# main.net
KiCad netlist of a schematic drawn in EAGLE
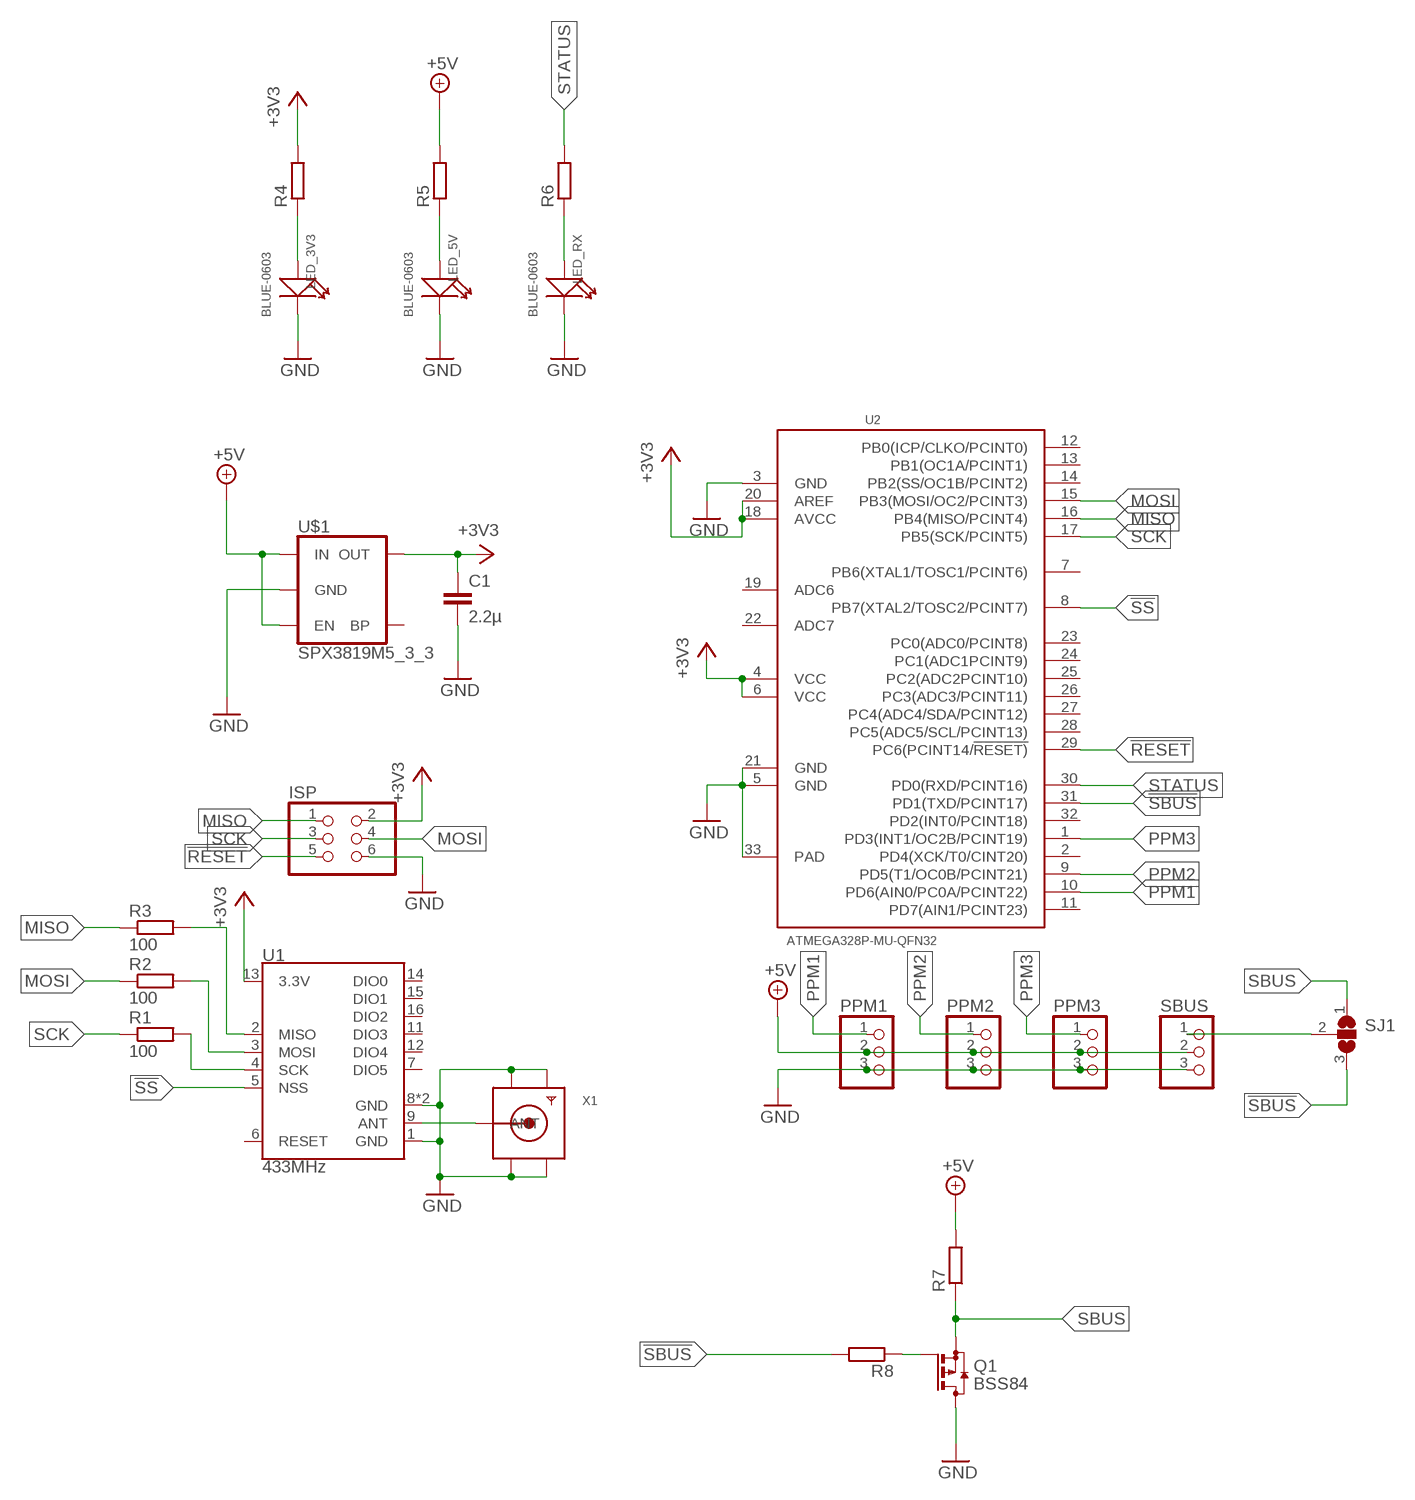
[diagram p0: schematic, sheet 1]

(export (version "E")
  (design (tool "Eeschema 10.0.6"))
  (components
    (comp (ref "C1")
      (value "2.2µ")
      (footprint "eagle-import:C0603")
      (libsource (lib "eagle-import") (part "C-EUC0603"))
    )
    (comp (ref "ISP")
      (value "PINHD-2X3_2.54-SMD")
      (footprint "eagle-import:2X03SMD")
      (libsource (lib "eagle-import") (part "PINHD-2X3_2.54-SMD"))
    )
    (comp (ref "LED_3V3")
      (value "BLUE-0603")
      (footprint "eagle-import:LED-0603")
      (fields (field (name "MPN") "19-217-BHC-ZL1M2RY-3T"))
      (libsource (lib "eagle-import") (part "SMD-LED-CLEAR-BLUE(0603)"))
    )
    (comp (ref "LED_5V")
      (value "BLUE-0603")
      (footprint "eagle-import:LED-0603")
      (fields (field (name "MPN") "19-217-BHC-ZL1M2RY-3T"))
      (libsource (lib "eagle-import") (part "SMD-LED-CLEAR-BLUE(0603)"))
    )
    (comp (ref "LED_RX")
      (value "BLUE-0603")
      (footprint "eagle-import:LED-0603")
      (fields (field (name "MPN") "19-217-BHC-ZL1M2RY-3T"))
      (libsource (lib "eagle-import") (part "SMD-LED-CLEAR-BLUE(0603)"))
    )
    (comp (ref "PPM1")
      (value "PINHD-1X3_2.54-SMD")
      (footprint "eagle-import:1X03SMD")
      (libsource (lib "eagle-import") (part "PINHD-1X3_2.54-SMD"))
    )
    (comp (ref "PPM2")
      (value "PINHD-1X3_2.54-SMD")
      (footprint "eagle-import:1X03SMD")
      (libsource (lib "eagle-import") (part "PINHD-1X3_2.54-SMD"))
    )
    (comp (ref "PPM3")
      (value "PINHD-1X3_2.54-SMD")
      (footprint "eagle-import:1X03SMD")
      (libsource (lib "eagle-import") (part "PINHD-1X3_2.54-SMD"))
    )
    (comp (ref "Q1")
      (value "BSS84")
      (footprint "eagle-import:SOT23")
      (libsource (lib "eagle-import") (part "BSS84"))
    )
    (comp (ref "R1")
      (value "100")
      (footprint "eagle-import:R0603")
      (libsource (lib "eagle-import") (part "R-EU_R0603"))
    )
    (comp (ref "R2")
      (value "100")
      (footprint "eagle-import:R0603")
      (libsource (lib "eagle-import") (part "R-EU_R0603"))
    )
    (comp (ref "R3")
      (value "100")
      (footprint "eagle-import:R0603")
      (libsource (lib "eagle-import") (part "R-EU_R0603"))
    )
    (comp (ref "R4")
      (value "R-EU_R0603")
      (footprint "eagle-import:R0603")
      (libsource (lib "eagle-import") (part "R-EU_R0603"))
    )
    (comp (ref "R5")
      (value "R-EU_R0603")
      (footprint "eagle-import:R0603")
      (libsource (lib "eagle-import") (part "R-EU_R0603"))
    )
    (comp (ref "R6")
      (value "R-EU_R0603")
      (footprint "eagle-import:R0603")
      (libsource (lib "eagle-import") (part "R-EU_R0603"))
    )
    (comp (ref "R7")
      (value "R-EU_R0603")
      (footprint "eagle-import:R0603")
      (libsource (lib "eagle-import") (part "R-EU_R0603"))
    )
    (comp (ref "R8")
      (value "R-EU_R0603")
      (footprint "eagle-import:R0603")
      (libsource (lib "eagle-import") (part "R-EU_R0603"))
    )
    (comp (ref "SBUS")
      (value "PINHD-1X3_2.54-SMD")
      (footprint "eagle-import:1X03SMD")
      (libsource (lib "eagle-import") (part "PINHD-1X3_2.54-SMD"))
    )
    (comp (ref "SJ1")
      (value "SJ2W")
      (footprint "eagle-import:SJ_2")
      (libsource (lib "eagle-import") (part "SJ2W"))
    )
    (comp (ref "U$1")
      (value "SPX3819M5_3_3")
      (footprint "eagle-import:SOT23-5")
      (libsource (lib "eagle-import") (part "V_REG_SPX3819-SOT23-5"))
    )
    (comp (ref "U1")
      (value "433MHz")
      (footprint "eagle-import:RFM69HCW-XXXS2")
      (libsource (lib "eagle-import") (part "RFM69HCW-433"))
    )
    (comp (ref "U2")
      (value "ATMEGA328P-MU-QFN32")
      (footprint "eagle-import:QFN32G-0.5-5X5MM")
      (fields (field (name "MPN") "ATMEGA328P-MU"))
      (libsource (lib "eagle-import") (part "MCU-ATMEGA328P-MU(QFN32)"))
    )
    (comp (ref "X1")
      (value "SMACONNECTOR_EDGE")
      (footprint "eagle-import:SMA_EDGELAUNCH")
      (libsource (lib "eagle-import") (part "SMACONNECTOR_EDGE"))
    )
  )
  (nets
    (net (code "1") (name "+3V3") (class "Default")
      (node (ref "C1") (pin "1") (pinfunction "1_1") (pintype "passive"))
      (node (ref "ISP") (pin "2") (pinfunction "2_2") (pintype "passive"))
      (node (ref "R4") (pin "2") (pinfunction "2_2") (pintype "passive"))
      (node (ref "U$1") (pin "5") (pinfunction "OUT_5") (pintype "passive"))
      (node (ref "U1") (pin "13") (pinfunction "3.3V_13") (pintype "power_in"))
      (node (ref "U2") (pin "18") (pinfunction "AVCC_18") (pintype "bidirectional"))
      (node (ref "U2") (pin "20") (pinfunction "AREF_20") (pintype "bidirectional"))
      (node (ref "U2") (pin "4") (pinfunction "VCC_4") (pintype "bidirectional"))
      (node (ref "U2") (pin "6") (pinfunction "VCC_6") (pintype "bidirectional"))
    )
    (net (code "2") (name "+5V") (class "Default")
      (node (ref "PPM1") (pin "2") (pinfunction "2_2") (pintype "passive"))
      (node (ref "PPM2") (pin "2") (pinfunction "2_2") (pintype "passive"))
      (node (ref "PPM3") (pin "2") (pinfunction "2_2") (pintype "passive"))
      (node (ref "R5") (pin "2") (pinfunction "2_2") (pintype "passive"))
      (node (ref "R7") (pin "2") (pinfunction "2_2") (pintype "passive"))
      (node (ref "SBUS") (pin "2") (pinfunction "2_2") (pintype "passive"))
      (node (ref "U$1") (pin "1") (pinfunction "IN_1") (pintype "input"))
      (node (ref "U$1") (pin "3") (pinfunction "EN_3") (pintype "input"))
    )
    (net (code "3") (name "/~{RESET}") (class "Default")
      (node (ref "ISP") (pin "5") (pinfunction "5_5") (pintype "passive"))
      (node (ref "U2") (pin "29") (pinfunction "PC6(PCINT14/~{RESET})_29") (pintype "bidirectional"))
    )
    (net (code "4") (name "/~{SBUS}") (class "Default")
      (node (ref "R8") (pin "2") (pinfunction "2_2") (pintype "passive"))
      (node (ref "SJ1") (pin "3") (pinfunction "3_3") (pintype "passive"))
      (node (ref "U2") (pin "31") (pinfunction "PD1(TXD/PCINT17)_31") (pintype "bidirectional"))
    )
    (net (code "5") (name "/~{SS}") (class "Default")
      (node (ref "U1") (pin "5") (pinfunction "NSS_5") (pintype "input"))
      (node (ref "U2") (pin "8") (pinfunction "PB7(XTAL2/TOSC2/PCINT7)_8") (pintype "bidirectional"))
    )
    (net (code "6") (name "GND") (class "Default")
      (node (ref "C1") (pin "2") (pinfunction "2_2") (pintype "passive"))
      (node (ref "ISP") (pin "6") (pinfunction "6_6") (pintype "passive"))
      (node (ref "LED_3V3") (pin "-") (pinfunction "-_-") (pintype "passive"))
      (node (ref "LED_5V") (pin "-") (pinfunction "-_-") (pintype "passive"))
      (node (ref "LED_RX") (pin "-") (pinfunction "-_-") (pintype "passive"))
      (node (ref "PPM1") (pin "3") (pinfunction "3_3") (pintype "passive"))
      (node (ref "PPM2") (pin "3") (pinfunction "3_3") (pintype "passive"))
      (node (ref "PPM3") (pin "3") (pinfunction "3_3") (pintype "passive"))
      (node (ref "Q1") (pin "3") (pinfunction "D_3") (pintype "passive"))
      (node (ref "SBUS") (pin "3") (pinfunction "3_3") (pintype "passive"))
      (node (ref "U$1") (pin "2") (pinfunction "GND_2") (pintype "input"))
      (node (ref "U1") (pin "1") (pinfunction "GND_1") (pintype "power_in"))
      (node (ref "U1") (pin "10") (pinfunction "GND_10") (pintype "power_in"))
      (node (ref "U1") (pin "8") (pinfunction "GND_8") (pintype "power_in"))
      (node (ref "U2") (pin "21") (pinfunction "GND_21") (pintype "bidirectional"))
      (node (ref "U2") (pin "3") (pinfunction "GND_3") (pintype "bidirectional"))
      (node (ref "U2") (pin "33") (pinfunction "PAD_33") (pintype "bidirectional"))
      (node (ref "U2") (pin "5") (pinfunction "GND_5") (pintype "bidirectional"))
      (node (ref "X1") (pin "GND@1") (pinfunction "GND4_GND@1") (pintype "power_in"))
      (node (ref "X1") (pin "GND@2") (pinfunction "GND3_GND@2") (pintype "power_in"))
      (node (ref "X1") (pin "GND@3") (pinfunction "GND2_GND@3") (pintype "power_in"))
      (node (ref "X1") (pin "GND@4") (pinfunction "GND1_GND@4") (pintype "power_in"))
    )
    (net (code "7") (name "MISO") (class "Default")
      (node (ref "ISP") (pin "1") (pinfunction "1_1") (pintype "passive"))
      (node (ref "R3") (pin "1") (pinfunction "1_1") (pintype "passive"))
      (node (ref "U2") (pin "16") (pinfunction "PB4(MISO/PCINT4)_16") (pintype "bidirectional"))
    )
    (net (code "8") (name "MOSI") (class "Default")
      (node (ref "ISP") (pin "4") (pinfunction "4_4") (pintype "passive"))
      (node (ref "R2") (pin "1") (pinfunction "1_1") (pintype "passive"))
      (node (ref "U2") (pin "15") (pinfunction "PB3(MOSI/OC2/PCINT3)_15") (pintype "bidirectional"))
    )
    (net (code "9") (name "Net-(LED_3V3-Pad+)") (class "Default")
      (node (ref "LED_3V3") (pin "+") (pinfunction "+_+") (pintype "passive"))
      (node (ref "R4") (pin "1") (pinfunction "1_1") (pintype "passive"))
    )
    (net (code "10") (name "Net-(LED_5V-Pad+)") (class "Default")
      (node (ref "LED_5V") (pin "+") (pinfunction "+_+") (pintype "passive"))
      (node (ref "R5") (pin "1") (pinfunction "1_1") (pintype "passive"))
    )
    (net (code "11") (name "Net-(LED_RX-Pad+)") (class "Default")
      (node (ref "LED_RX") (pin "+") (pinfunction "+_+") (pintype "passive"))
      (node (ref "R6") (pin "1") (pinfunction "1_1") (pintype "passive"))
    )
    (net (code "12") (name "Net-(Q1-G)") (class "Default")
      (node (ref "Q1") (pin "1") (pinfunction "G_1") (pintype "passive"))
      (node (ref "R8") (pin "1") (pinfunction "1_1") (pintype "passive"))
    )
    (net (code "13") (name "Net-(SBUS-Pad1)") (class "Default")
      (node (ref "SBUS") (pin "1") (pinfunction "1_1") (pintype "passive"))
      (node (ref "SJ1") (pin "2") (pinfunction "2_2") (pintype "passive"))
    )
    (net (code "14") (name "Net-(U1-ANT)") (class "Default")
      (node (ref "U1") (pin "9") (pinfunction "ANT_9") (pintype "passive"))
      (node (ref "X1") (pin "P") (pinfunction "ANT_P") (pintype "bidirectional"))
    )
    (net (code "15") (name "Net-(U1-MISO)") (class "Default")
      (node (ref "R3") (pin "2") (pinfunction "2_2") (pintype "passive"))
      (node (ref "U1") (pin "2") (pinfunction "MISO_2") (pintype "bidirectional"))
    )
    (net (code "16") (name "Net-(U1-MOSI)") (class "Default")
      (node (ref "R2") (pin "2") (pinfunction "2_2") (pintype "passive"))
      (node (ref "U1") (pin "3") (pinfunction "MOSI_3") (pintype "input"))
    )
    (net (code "17") (name "Net-(U1-SCK)") (class "Default")
      (node (ref "R1") (pin "2") (pinfunction "2_2") (pintype "passive"))
      (node (ref "U1") (pin "4") (pinfunction "SCK_4") (pintype "input"))
    )
    (net (code "18") (name "PPM1") (class "Default")
      (node (ref "PPM1") (pin "1") (pinfunction "1_1") (pintype "passive"))
      (node (ref "U2") (pin "10") (pinfunction "PD6(AIN0/PC0A/PCINT22)_10") (pintype "bidirectional"))
    )
    (net (code "19") (name "PPM2") (class "Default")
      (node (ref "PPM2") (pin "1") (pinfunction "1_1") (pintype "passive"))
      (node (ref "U2") (pin "9") (pinfunction "PD5(T1/OC0B/PCINT21)_9") (pintype "bidirectional"))
    )
    (net (code "20") (name "PPM3") (class "Default")
      (node (ref "PPM3") (pin "1") (pinfunction "1_1") (pintype "passive"))
      (node (ref "U2") (pin "1") (pinfunction "PD3(INT1/OC2B/PCINT19)_1") (pintype "bidirectional"))
    )
    (net (code "21") (name "SBUS") (class "Default")
      (node (ref "Q1") (pin "2") (pinfunction "S_2") (pintype "passive"))
      (node (ref "R7") (pin "1") (pinfunction "1_1") (pintype "passive"))
      (node (ref "SJ1") (pin "1") (pinfunction "1_1") (pintype "passive"))
    )
    (net (code "22") (name "SCK") (class "Default")
      (node (ref "ISP") (pin "3") (pinfunction "3_3") (pintype "passive"))
      (node (ref "R1") (pin "1") (pinfunction "1_1") (pintype "passive"))
      (node (ref "U2") (pin "17") (pinfunction "PB5(SCK/PCINT5)_17") (pintype "bidirectional"))
    )
    (net (code "23") (name "STATUS") (class "Default")
      (node (ref "R6") (pin "2") (pinfunction "2_2") (pintype "passive"))
      (node (ref "U2") (pin "30") (pinfunction "PD0(RXD/PCINT16)_30") (pintype "bidirectional"))
    )
    (net (code "24") (name "unconnected-(U$1-BP-Pad4)") (class "Default")
      (node (ref "U$1") (pin "4") (pinfunction "BP_4") (pintype "input"))
    )
    (net (code "25") (name "unconnected-(U1-DIO0-Pad14)") (class "Default")
      (node (ref "U1") (pin "14") (pinfunction "DIO0_14") (pintype "bidirectional"))
    )
    (net (code "26") (name "unconnected-(U1-DIO1-Pad15)") (class "Default")
      (node (ref "U1") (pin "15") (pinfunction "DIO1_15") (pintype "bidirectional"))
    )
    (net (code "27") (name "unconnected-(U1-DIO2-Pad16)") (class "Default")
      (node (ref "U1") (pin "16") (pinfunction "DIO2_16") (pintype "bidirectional"))
    )
    (net (code "28") (name "unconnected-(U1-DIO3-Pad11)") (class "Default")
      (node (ref "U1") (pin "11") (pinfunction "DIO3_11") (pintype "bidirectional"))
    )
    (net (code "29") (name "unconnected-(U1-DIO4-Pad12)") (class "Default")
      (node (ref "U1") (pin "12") (pinfunction "DIO4_12") (pintype "bidirectional"))
    )
    (net (code "30") (name "unconnected-(U1-DIO5-Pad7)") (class "Default")
      (node (ref "U1") (pin "7") (pinfunction "DIO5_7") (pintype "bidirectional"))
    )
    (net (code "31") (name "unconnected-(U1-RESET-Pad6)") (class "Default")
      (node (ref "U1") (pin "6") (pinfunction "RESET_6") (pintype "input"))
    )
    (net (code "32") (name "unconnected-(U2-ADC6-Pad19)") (class "Default")
      (node (ref "U2") (pin "19") (pinfunction "ADC6_19") (pintype "bidirectional"))
    )
    (net (code "33") (name "unconnected-(U2-ADC7-Pad22)") (class "Default")
      (node (ref "U2") (pin "22") (pinfunction "ADC7_22") (pintype "bidirectional"))
    )
    (net (code "34") (name "unconnected-(U2-PB0(ICP{slash}CLKO{slash}PCINT0)-Pad12)") (class "Default")
      (node (ref "U2") (pin "12") (pinfunction "PB0(ICP/CLKO/PCINT0)_12") (pintype "bidirectional"))
    )
    (net (code "35") (name "unconnected-(U2-PB1(OC1A{slash}PCINT1)-Pad13)") (class "Default")
      (node (ref "U2") (pin "13") (pinfunction "PB1(OC1A/PCINT1)_13") (pintype "bidirectional"))
    )
    (net (code "36") (name "unconnected-(U2-PB2(SS{slash}OC1B{slash}PCINT2)-Pad14)") (class "Default")
      (node (ref "U2") (pin "14") (pinfunction "PB2(SS/OC1B/PCINT2)_14") (pintype "bidirectional"))
    )
    (net (code "37") (name "unconnected-(U2-PB6(XTAL1{slash}TOSC1{slash}PCINT6)-Pad7)") (class "Default")
      (node (ref "U2") (pin "7") (pinfunction "PB6(XTAL1/TOSC1/PCINT6)_7") (pintype "bidirectional"))
    )
    (net (code "38") (name "unconnected-(U2-PC0(ADC0{slash}PCINT8)-Pad23)") (class "Default")
      (node (ref "U2") (pin "23") (pinfunction "PC0(ADC0/PCINT8)_23") (pintype "bidirectional"))
    )
    (net (code "39") (name "unconnected-(U2-PC1(ADC1PCINT9)-Pad24)") (class "Default")
      (node (ref "U2") (pin "24") (pinfunction "PC1(ADC1PCINT9)_24") (pintype "bidirectional"))
    )
    (net (code "40") (name "unconnected-(U2-PC2(ADC2PCINT10)-Pad25)") (class "Default")
      (node (ref "U2") (pin "25") (pinfunction "PC2(ADC2PCINT10)_25") (pintype "bidirectional"))
    )
    (net (code "41") (name "unconnected-(U2-PC3(ADC3{slash}PCINT11)-Pad26)") (class "Default")
      (node (ref "U2") (pin "26") (pinfunction "PC3(ADC3/PCINT11)_26") (pintype "bidirectional"))
    )
    (net (code "42") (name "unconnected-(U2-PC4(ADC4{slash}SDA{slash}PCINT12)-Pad27)") (class "Default")
      (node (ref "U2") (pin "27") (pinfunction "PC4(ADC4/SDA/PCINT12)_27") (pintype "bidirectional"))
    )
    (net (code "43") (name "unconnected-(U2-PC5(ADC5{slash}SCL{slash}PCINT13)-Pad28)") (class "Default")
      (node (ref "U2") (pin "28") (pinfunction "PC5(ADC5/SCL/PCINT13)_28") (pintype "bidirectional"))
    )
    (net (code "44") (name "unconnected-(U2-PD2(INT0{slash}PCINT18)-Pad32)") (class "Default")
      (node (ref "U2") (pin "32") (pinfunction "PD2(INT0/PCINT18)_32") (pintype "bidirectional"))
    )
    (net (code "45") (name "unconnected-(U2-PD4(XCK{slash}T0{slash}CINT20)-Pad2)") (class "Default")
      (node (ref "U2") (pin "2") (pinfunction "PD4(XCK/T0/CINT20)_2") (pintype "bidirectional"))
    )
    (net (code "46") (name "unconnected-(U2-PD7(AIN1{slash}PCINT23)-Pad11)") (class "Default")
      (node (ref "U2") (pin "11") (pinfunction "PD7(AIN1/PCINT23)_11") (pintype "bidirectional"))
    )
  )
)
